# TFT-Display.net
KiCad netlist of a schematic drawn in Altium Designer
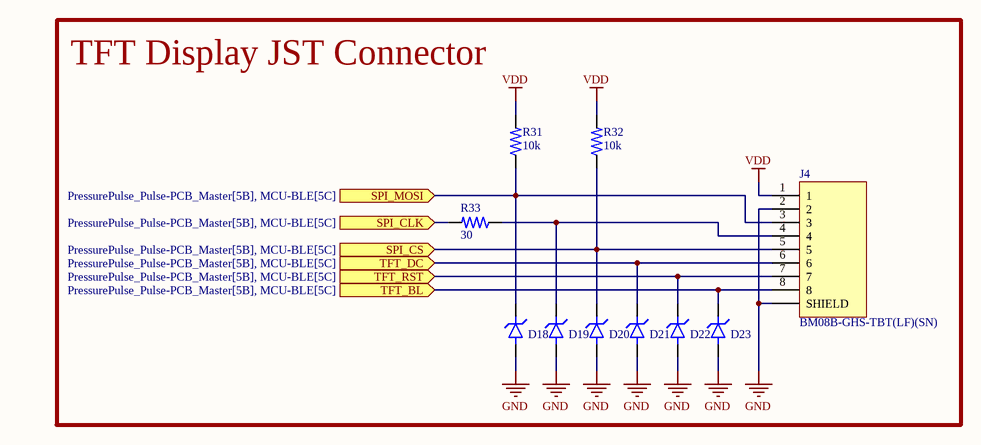
[diagram p0: TFT-Display.SchDoc]

(export (version "E")
  (design (tool "Eeschema 10.0.6"))
  (components
    (comp (ref "D18")
      (value "BDFN2C051V40")
      (footprint "PressurePulse:BDFN2C051V40")
      (description "25V Clamp 4A (8/20µs) Ipp Tvs Diode Surface Mount SLP1006P2")
      (fields (field (name "MFR") "BORN"))
      (libsource (lib "PressurePulse") (part "TVS DIODE"))
    )
    (comp (ref "D19")
      (value "BDFN2C051V40")
      (footprint "PressurePulse:BDFN2C051V40")
      (description "25V Clamp 4A (8/20µs) Ipp Tvs Diode Surface Mount SLP1006P2")
      (fields (field (name "MFR") "BORN"))
      (libsource (lib "PressurePulse") (part "TVS DIODE"))
    )
    (comp (ref "D20")
      (value "BDFN2C051V40")
      (footprint "PressurePulse:BDFN2C051V40")
      (description "25V Clamp 4A (8/20µs) Ipp Tvs Diode Surface Mount SLP1006P2")
      (fields (field (name "MFR") "BORN"))
      (libsource (lib "PressurePulse") (part "TVS DIODE"))
    )
    (comp (ref "D21")
      (value "BDFN2C051V40")
      (footprint "PressurePulse:BDFN2C051V40")
      (description "25V Clamp 4A (8/20µs) Ipp Tvs Diode Surface Mount SLP1006P2")
      (fields (field (name "MFR") "BORN"))
      (libsource (lib "PressurePulse") (part "TVS DIODE"))
    )
    (comp (ref "D22")
      (value "BDFN2C051V40")
      (footprint "PressurePulse:BDFN2C051V40")
      (description "25V Clamp 4A (8/20µs) Ipp Tvs Diode Surface Mount SLP1006P2")
      (fields (field (name "MFR") "BORN"))
      (libsource (lib "PressurePulse") (part "TVS DIODE"))
    )
    (comp (ref "D23")
      (value "BDFN2C051V40")
      (footprint "PressurePulse:BDFN2C051V40")
      (description "25V Clamp 4A (8/20µs) Ipp Tvs Diode Surface Mount SLP1006P2")
      (fields (field (name "MFR") "BORN"))
      (libsource (lib "PressurePulse") (part "TVS DIODE"))
    )
    (comp (ref "J4")
      (value "BM08B-GHS-TBT(LF)(SN)")
      (footprint "PressurePulse:JST_BM08B-GHS-TBT(LF)(SN)(N)")
      (description "Connector Header Surface Mount 8 position 0.049 _1.25mm_")
      (fields (field (name "MFR") "JST Sales"))
      (libsource (lib "PressurePulse") (part "JST CONN 8POS GH"))
    )
    (comp (ref "R31")
      (value "10k")
      (footprint "PressurePulse:0402R")
      (description "Resistor")
      (fields (field (name "Comment") "RES"))
      (libsource (lib "PressurePulse") (part "RES"))
    )
    (comp (ref "R32")
      (value "10k")
      (footprint "PressurePulse:0402R")
      (description "Resistor")
      (fields (field (name "Comment") "RES"))
      (libsource (lib "PressurePulse") (part "RES"))
    )
    (comp (ref "R33")
      (value "30")
      (footprint "PressurePulse:0402R")
      (description "Resistor")
      (fields (field (name "Comment") "RES"))
      (libsource (lib "PressurePulse") (part "RES"))
    )
  )
  (nets
    (net (code "1") (name "/SPI_CLK") (class "Default")
      (node (ref "R33") (pin "2") (pinfunction "2_2") (pintype "passive"))
    )
    (net (code "2") (name "/SPI_CS") (class "Default")
      (node (ref "D20") (pin "K") (pinfunction "K_K") (pintype "passive"))
      (node (ref "J4") (pin "5") (pinfunction "5_5") (pintype "passive"))
      (node (ref "R32") (pin "1") (pinfunction "1_1") (pintype "passive"))
    )
    (net (code "3") (name "/SPI_MOSI") (class "Default")
      (node (ref "D18") (pin "K") (pinfunction "K_K") (pintype "passive"))
      (node (ref "J4") (pin "3") (pinfunction "3_3") (pintype "passive"))
      (node (ref "R31") (pin "1") (pinfunction "1_1") (pintype "passive"))
    )
    (net (code "4") (name "/TFT_BL") (class "Default")
      (node (ref "D23") (pin "K") (pinfunction "K_K") (pintype "passive"))
      (node (ref "J4") (pin "8") (pinfunction "8_8") (pintype "passive"))
    )
    (net (code "5") (name "/TFT_DC") (class "Default")
      (node (ref "D21") (pin "K") (pinfunction "K_K") (pintype "passive"))
      (node (ref "J4") (pin "6") (pinfunction "6_6") (pintype "passive"))
    )
    (net (code "6") (name "/TFT_RST") (class "Default")
      (node (ref "D22") (pin "K") (pinfunction "K_K") (pintype "passive"))
      (node (ref "J4") (pin "7") (pinfunction "7_7") (pintype "passive"))
    )
    (net (code "7") (name "GND") (class "Default")
      (node (ref "D18") (pin "A") (pinfunction "A_A") (pintype "passive"))
      (node (ref "D19") (pin "A") (pinfunction "A_A") (pintype "passive"))
      (node (ref "D20") (pin "A") (pinfunction "A_A") (pintype "passive"))
      (node (ref "D21") (pin "A") (pinfunction "A_A") (pintype "passive"))
      (node (ref "D22") (pin "A") (pinfunction "A_A") (pintype "passive"))
      (node (ref "D23") (pin "A") (pinfunction "A_A") (pintype "passive"))
      (node (ref "J4") (pin "2") (pinfunction "2_2") (pintype "passive"))
      (node (ref "J4") (pin "SHIELD") (pinfunction "SHIELD_SHIELD") (pintype "passive"))
    )
    (net (code "8") (name "Net-(D19-PadK)") (class "Default")
      (node (ref "D19") (pin "K") (pinfunction "K_K") (pintype "passive"))
      (node (ref "J4") (pin "4") (pinfunction "4_4") (pintype "passive"))
      (node (ref "R33") (pin "1") (pinfunction "1_1") (pintype "passive"))
    )
    (net (code "9") (name "VDD") (class "Default")
      (node (ref "J4") (pin "1") (pinfunction "1_1") (pintype "passive"))
      (node (ref "R31") (pin "2") (pinfunction "2_2") (pintype "passive"))
      (node (ref "R32") (pin "2") (pinfunction "2_2") (pintype "passive"))
    )
  )
)
